# STM32_ESP.net
KiCad netlist of a schematic drawn in Altium Designer
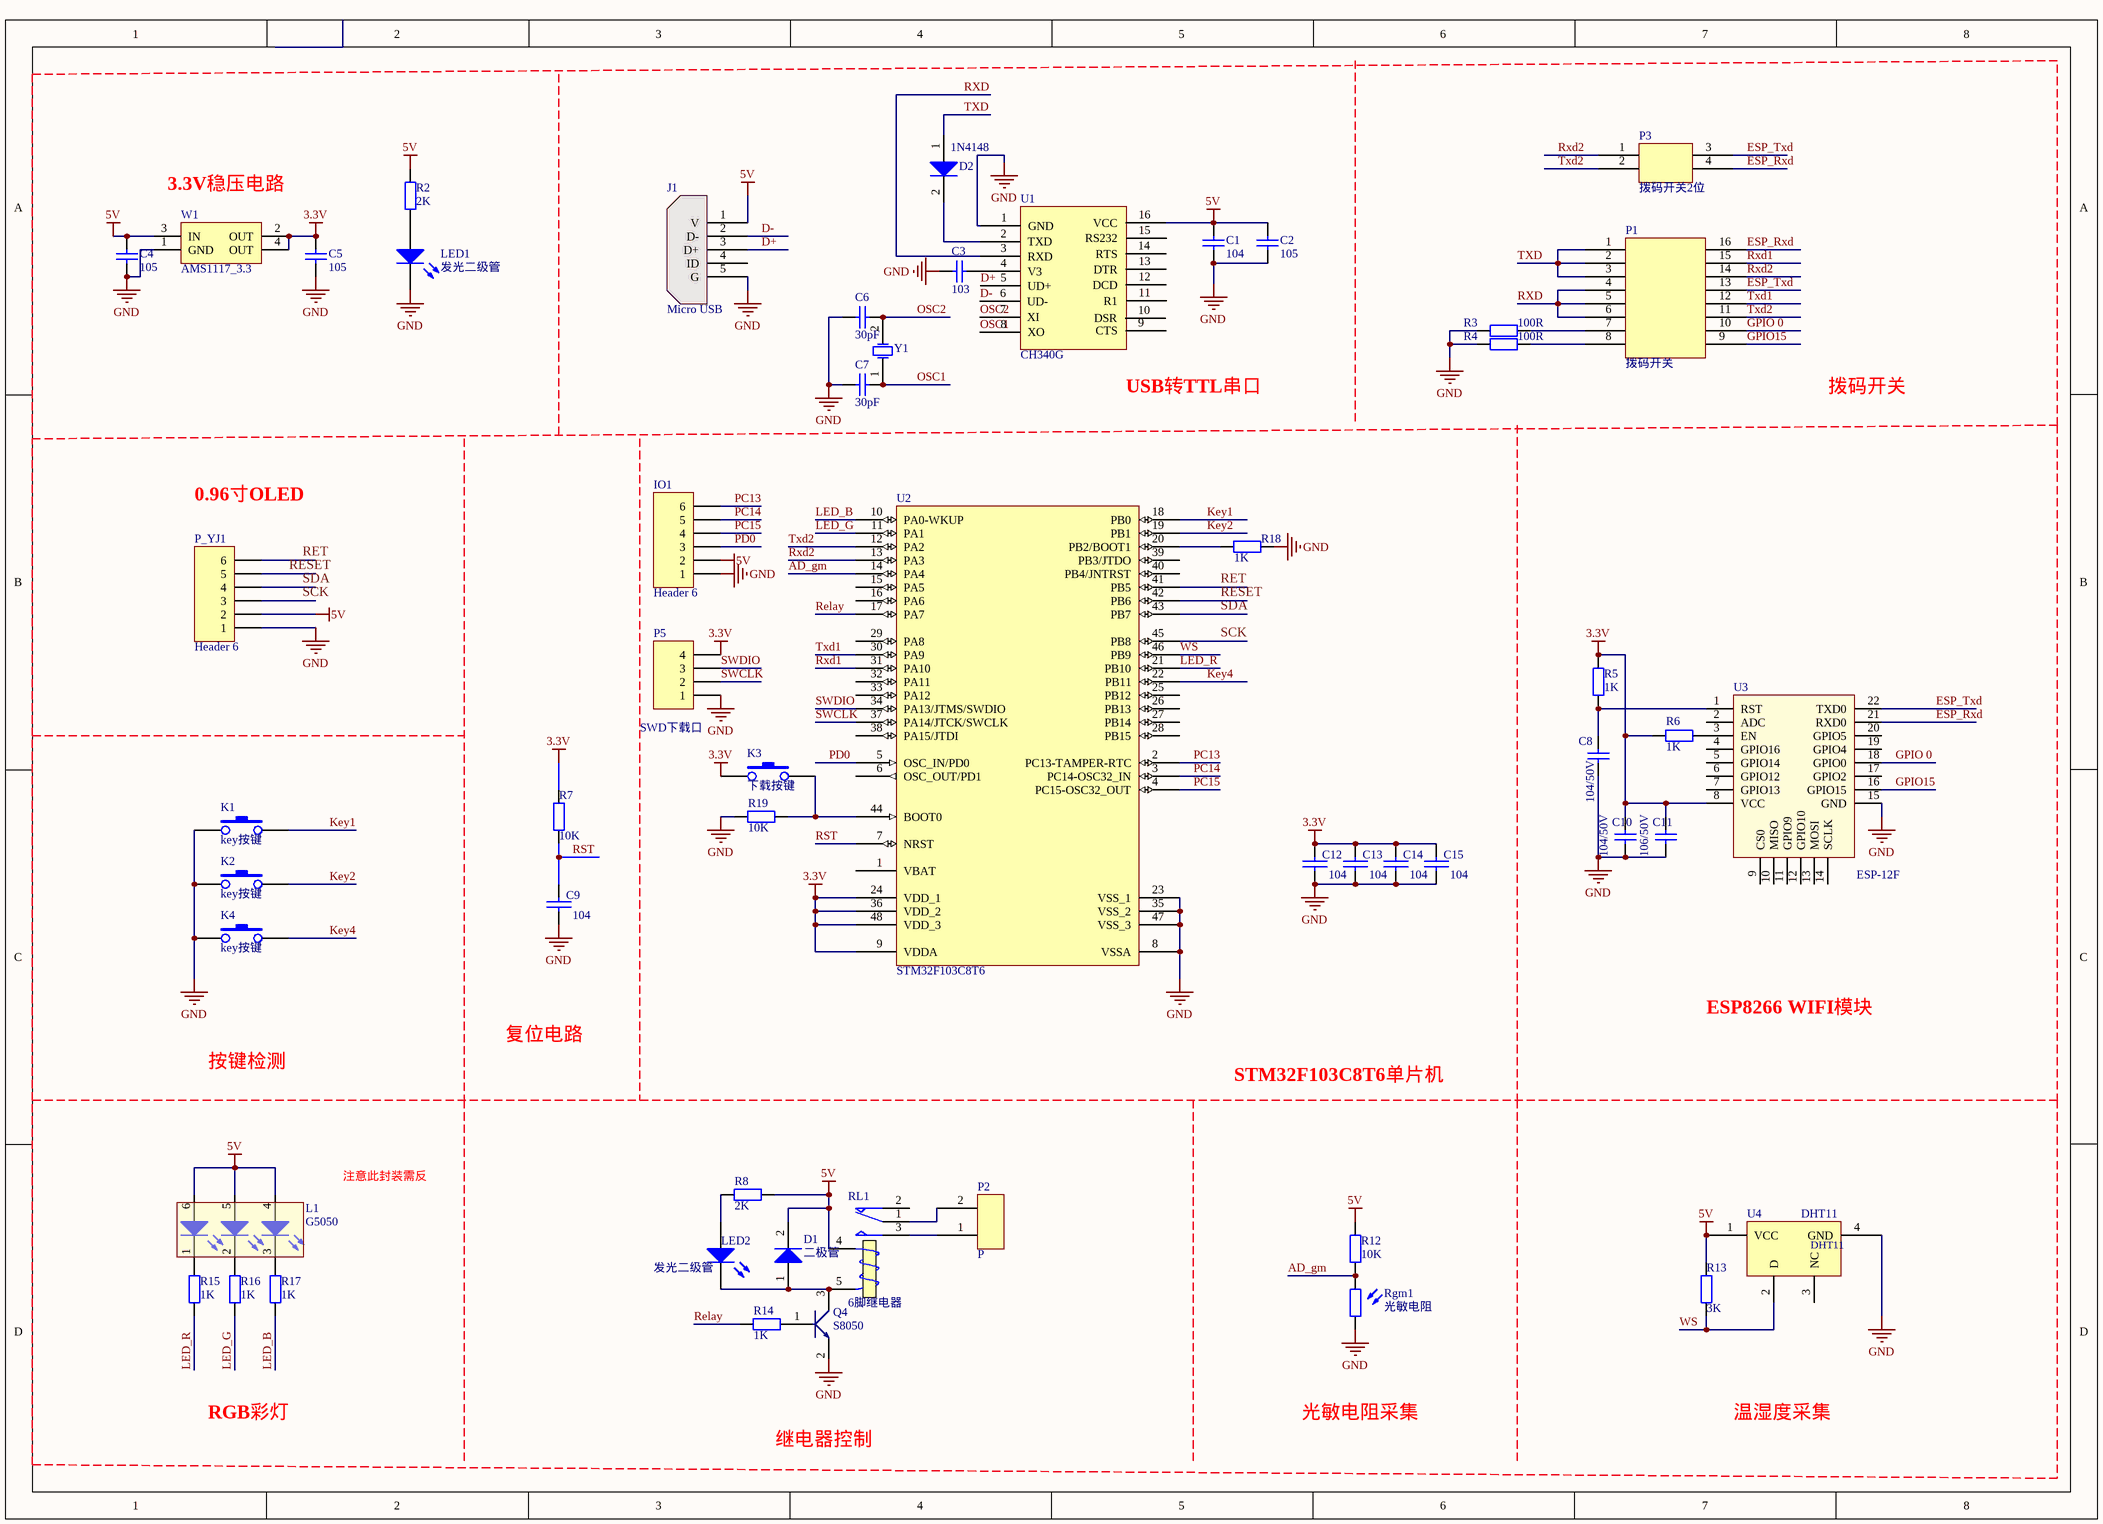
[diagram p0: STM32&ESP.SchDoc]

(export (version "E")
  (design (tool "Eeschema 10.0.6"))
  (components
    (comp (ref "C1")
      (value "104")
      (footprint "SC0603")
      (description "Capacitor")
      (fields (field (name "Comment") "Cap") (field (name "PUBLISHER") "Altium Limited"))
      (libsource (lib "myintlib") (part "Cap"))
    )
    (comp (ref "C2")
      (value "105")
      (footprint "SC0603")
      (description "Capacitor")
      (fields (field (name "Comment") "Cap") (field (name "PUBLISHER") "Altium Limited"))
      (libsource (lib "myintlib") (part "Cap"))
    )
    (comp (ref "C3")
      (value "103")
      (footprint "SC0603")
      (description "Capacitor")
      (fields (field (name "Comment") "Cap") (field (name "PUBLISHER") "Altium Limited"))
      (libsource (lib "myintlib") (part "Cap"))
    )
    (comp (ref "C4")
      (value "105")
      (footprint "SC0603")
      (description "Capacitor")
      (fields (field (name "Comment") "Cap") (field (name "PUBLISHER") "Altium Limited"))
      (libsource (lib "myintlib") (part "Cap"))
    )
    (comp (ref "C5")
      (value "105")
      (footprint "SC0603")
      (description "Capacitor")
      (fields (field (name "Comment") "Cap") (field (name "PUBLISHER") "Altium Limited"))
      (libsource (lib "myintlib") (part "Cap"))
    )
    (comp (ref "C6")
      (value "30pF")
      (footprint "SC0603")
      (description "Capacitor")
      (fields (field (name "Comment") "Cap") (field (name "PUBLISHER") "Altium Limited"))
      (libsource (lib "Miscellaneous Devices") (part "Cap"))
    )
    (comp (ref "C7")
      (value "30pF")
      (footprint "SC0603")
      (description "Capacitor")
      (fields (field (name "Comment") "Cap") (field (name "PUBLISHER") "Altium Limited"))
      (libsource (lib "Miscellaneous Devices") (part "Cap"))
    )
    (comp (ref "C8")
      (value "104/50V")
      (footprint "SC0603")
      (description "Capacitor (Semiconductor SIM Model)")
      (fields (field (name "MANUFACTURER") "风华高科"))
      (libsource (lib "Miscellaneous Devices") (part "Cap Semi"))
    )
    (comp (ref "C9")
      (value "104")
      (footprint "SC0603")
      (description "Capacitor")
      (libsource (lib "*") (part "CAP"))
    )
    (comp (ref "C10")
      (value "104/50V")
      (footprint "SC0603")
      (description "Capacitor (Semiconductor SIM Model)")
      (fields (field (name "MANUFACTURER") "风华高科"))
      (libsource (lib "Miscellaneous Devices") (part "Cap Semi"))
    )
    (comp (ref "C11")
      (value "106/50V")
      (footprint "SC0603")
      (description "Capacitor (Semiconductor SIM Model)")
      (fields (field (name "MANUFACTURER") "风华高科"))
      (libsource (lib "Miscellaneous Devices") (part "Cap Semi"))
    )
    (comp (ref "C12")
      (value "104")
      (footprint "SC0603")
      (description "Capacitor")
      (libsource (lib "*") (part "CAP"))
    )
    (comp (ref "C13")
      (value "104")
      (footprint "SC0603")
      (description "Capacitor")
      (libsource (lib "*") (part "CAP"))
    )
    (comp (ref "C14")
      (value "104")
      (footprint "SC0603")
      (description "Capacitor")
      (libsource (lib "*") (part "CAP"))
    )
    (comp (ref "C15")
      (value "104")
      (footprint "SC0603")
      (description "Capacitor")
      (libsource (lib "*") (part "CAP"))
    )
    (comp (ref "D1") (value "二极管") (footprint "SS12") (libsource (lib "单片机1") (part "二极管")))
    (comp (ref "D2") (value "1N4148") (footprint "SS12") (libsource (lib "单片机1") (part "二极管")))
    (comp (ref "IO1")
      (value "Header 6")
      (footprint "HDR1X6")
      (description "Header, 6-Pin")
      (fields (field (name "PUBLISHER") "Altium Limited"))
      (libsource (lib "Miscellaneous Connectors") (part "Header 6"))
    )
    (comp (ref "J1") (value "Micro USB") (footprint "micro usb") (libsource (lib "各种接插件") (part "Micro USB")))
    (comp (ref "K1") (value "key按键") (footprint "SW-T") (libsource (lib "单片机1") (part "key按键")))
    (comp (ref "K2") (value "key按键") (footprint "SW-T") (libsource (lib "单片机1") (part "key按键")))
    (comp (ref "K3") (value "下载按键") (footprint "轻触开关 3*6*2.5mm") (libsource (lib "单片机1") (part "key按键")))
    (comp (ref "K4") (value "key按键") (footprint "SW-T") (libsource (lib "单片机1") (part "key按键")))
    (comp (ref "L1") (value "G5050") (footprint "G5050") (libsource (lib "各种显示器件") (part "G5050")))
    (comp (ref "LED1") (value "发光二级管") (footprint "G0603") (libsource (lib "单片机1") (part "发光二级管")))
    (comp (ref "LED2") (value "发光二级管") (footprint "G0603") (libsource (lib "单片机1") (part "发光二级管")))
    (comp (ref "P1") (value "拨码开关") (footprint "拨码开关") (libsource (lib "单片机1") (part "拨码开关")))
    (comp (ref "P2") (value "P") (footprint "KF301-2P") (libsource (lib "各种接插件") (part "2P")))
    (comp (ref "P3") (value "拨码开关2位") (footprint "拨码开关2位") (libsource (lib "单片机1") (part "拨码开关2位")))
    (comp (ref "P5") (value "SWD下载口") (footprint "4P") (libsource (lib "单片机1") (part "4P")))
    (comp (ref "P_YJ1")
      (value "Header 6")
      (footprint "HDR1X6")
      (description "Header, 6-Pin")
      (fields (field (name "PUBLISHER") "Altium Limited"))
      (libsource (lib "Miscellaneous Connectors") (part "Header 6"))
    )
    (comp (ref "Q4") (value "S8050") (footprint "SOT-23") (libsource (lib "单片机1") (part "三极管3")))
    (comp (ref "R2") (value "2K") (footprint "0603R") (libsource (lib "单片机1") (part "电阻R")))
    (comp (ref "R3")
      (value "100R")
      (footprint "0603R")
      (fields (field (name "MANUFACTURER") "厚生"))
      (libsource (lib "YANG") (part "RES0.2"))
    )
    (comp (ref "R4")
      (value "100R")
      (footprint "0603R")
      (fields (field (name "MANUFACTURER") "厚生"))
      (libsource (lib "YANG") (part "RES0.2"))
    )
    (comp (ref "R5")
      (value "1K")
      (footprint "0603R")
      (fields (field (name "MANUFACTURER") "厚生"))
      (libsource (lib "") (part "RES0.2_1"))
    )
    (comp (ref "R6")
      (value "1K")
      (footprint "0603R")
      (fields (field (name "MANUFACTURER") "厚生"))
      (libsource (lib "YANG") (part "RES0.2"))
    )
    (comp (ref "R7")
      (value "1K")
      (footprint "0603R")
      (fields (field (name "ALTIUM_UNNAMED_1") "10K"))
      (libsource (lib "") (part "RES0.4_1"))
    )
    (comp (ref "R8") (value "2K") (footprint "0603R") (libsource (lib "") (part "电阻R_1")))
    (comp (ref "R12")
      (value "10K")
      (footprint "0603R")
      (fields (field (name "MANUFACTURER") "厚生"))
      (libsource (lib "") (part "RES0.2_1"))
    )
    (comp (ref "R13")
      (value "1K")
      (footprint "0603R")
      (fields (field (name "ALTIUM_UNNAMED_1") "3K"))
      (libsource (lib "YANG") (part "RES0.4"))
    )
    (comp (ref "R14")
      (value "1K")
      (footprint "0603R")
      (fields (field (name "MANUFACTURER") "厚生"))
      (libsource (lib "YANG") (part "RES0.2"))
    )
    (comp (ref "R15")
      (value "1K")
      (footprint "0603R")
      (fields (field (name "MANUFACTURER") "厚生"))
      (libsource (lib "") (part "RES0.2_1"))
    )
    (comp (ref "R16")
      (value "1K")
      (footprint "0603R")
      (fields (field (name "MANUFACTURER") "厚生"))
      (libsource (lib "") (part "RES0.2_1"))
    )
    (comp (ref "R17")
      (value "1K")
      (footprint "0603R")
      (fields (field (name "MANUFACTURER") "厚生"))
      (libsource (lib "") (part "RES0.2_1"))
    )
    (comp (ref "R18")
      (value "1K")
      (footprint "0603R")
      (fields (field (name "MANUFACTURER") "厚生"))
      (libsource (lib "") (part "RES0.2_2"))
    )
    (comp (ref "R19")
      (value "10K")
      (footprint "0603R")
      (fields (field (name "MANUFACTURER") "厚生"))
      (libsource (lib "YANG") (part "RES0.2"))
    )
    (comp (ref "Rgm1") (value "光敏电阻") (footprint "pr") (libsource (lib "电阻") (part "Res-Sen")))
    (comp (ref "RL1") (value "6脚继电器") (footprint "6脚继电器") (libsource (lib "单片机1") (part "6脚继电器")))
    (comp (ref "U1") (value "CH340G") (footprint "MAX3232") (libsource (lib "单片机1") (part "CH340G")))
    (comp (ref "U2")
      (value "STM32F103C8T6")
      (footprint "LQFP-48_M")
      (libsource (lib "单片机1") (part "STM32F103C8T6"))
    )
    (comp (ref "U3")
      (value "ESP-12F")
      (footprint "ESP12F")
      (fields (field (name "MANUFACTURER") "安信可"))
      (libsource (lib "其他") (part "ESP-12F"))
    )
    (comp (ref "U4") (value "DHT11") (footprint "DHT11") (libsource (lib "其他") (part "DHT11")))
    (comp (ref "W1")
      (value "AMS1117_3.3")
      (footprint "AMS1117_3.3")
      (libsource (lib "单片机1") (part "AMS1117_3.3"))
    )
    (comp (ref "Y1")
      (value "XTAL")
      (footprint "XTAX5")
      (description "Crystal Oscillator")
      (fields (field (name "PUBLISHER") "Altium Limited"))
      (libsource (lib "Miscellaneous Devices") (part "XTAL"))
    )
  )
  (nets
    (net (code "1") (name "/AD_gm") (class "Default")
      (node (ref "R12") (pin "1") (pinfunction "1_1") (pintype "passive"))
      (node (ref "Rgm1") (pin "1") (pinfunction "1_1") (pintype "passive"))
      (node (ref "U2") (pin "14") (pinfunction "PA4_14") (pintype "bidirectional"))
    )
    (net (code "2") (name "/D+") (class "Default")
      (node (ref "J1") (pin "3") (pinfunction "D+_3") (pintype "passive"))
      (node (ref "U1") (pin "5") (pinfunction "UD+_5") (pintype "passive"))
    )
    (net (code "3") (name "/D-") (class "Default")
      (node (ref "J1") (pin "2") (pinfunction "D-_2") (pintype "passive"))
      (node (ref "U1") (pin "6") (pinfunction "UD-_6") (pintype "passive"))
    )
    (net (code "4") (name "/ESP_Rxd") (class "Default")
      (node (ref "P1") (pin "16") (pinfunction "16_16") (pintype "passive"))
      (node (ref "P3") (pin "4") (pinfunction "4_4") (pintype "passive"))
      (node (ref "U3") (pin "21") (pinfunction "RXD0_21") (pintype "passive"))
    )
    (net (code "5") (name "/ESP_Txd") (class "Default")
      (node (ref "P1") (pin "13") (pinfunction "13_13") (pintype "passive"))
      (node (ref "P3") (pin "3") (pinfunction "3_3") (pintype "passive"))
      (node (ref "U3") (pin "22") (pinfunction "TXD0_22") (pintype "passive"))
    )
    (net (code "6") (name "/GPIO 0") (class "Default")
      (node (ref "P1") (pin "10") (pinfunction "10_10") (pintype "passive"))
      (node (ref "U3") (pin "18") (pinfunction "GPIO0_18") (pintype "passive"))
    )
    (net (code "7") (name "/GPIO15") (class "Default")
      (node (ref "P1") (pin "9") (pinfunction "9_9") (pintype "passive"))
      (node (ref "U3") (pin "16") (pinfunction "GPIO15_16") (pintype "passive"))
    )
    (net (code "8") (name "/Key1") (class "Default")
      (node (ref "K1") (pin "2") (pinfunction "2_2") (pintype "passive"))
      (node (ref "U2") (pin "18") (pinfunction "PB0_18") (pintype "bidirectional"))
    )
    (net (code "9") (name "/Key2") (class "Default")
      (node (ref "K2") (pin "2") (pinfunction "2_2") (pintype "passive"))
      (node (ref "U2") (pin "19") (pinfunction "PB1_19") (pintype "bidirectional"))
    )
    (net (code "10") (name "/Key4") (class "Default")
      (node (ref "K4") (pin "2") (pinfunction "2_2") (pintype "passive"))
      (node (ref "U2") (pin "22") (pinfunction "PB11_22") (pintype "bidirectional"))
    )
    (net (code "11") (name "/LED_B") (class "Default")
      (node (ref "R17") (pin "1") (pinfunction "1_1") (pintype "passive"))
      (node (ref "U2") (pin "10") (pinfunction "PA0-WKUP_10") (pintype "bidirectional"))
    )
    (net (code "12") (name "/LED_G") (class "Default")
      (node (ref "R16") (pin "1") (pinfunction "1_1") (pintype "passive"))
      (node (ref "U2") (pin "11") (pinfunction "PA1_11") (pintype "bidirectional"))
    )
    (net (code "13") (name "/LED_R") (class "Default")
      (node (ref "R15") (pin "1") (pinfunction "1_1") (pintype "passive"))
      (node (ref "U2") (pin "21") (pinfunction "PB10_21") (pintype "bidirectional"))
    )
    (net (code "14") (name "/OSC1") (class "Default")
      (node (ref "C7") (pin "1") (pinfunction "1_1") (pintype "passive"))
      (node (ref "U1") (pin "8") (pinfunction "XO_8") (pintype "passive"))
      (node (ref "Y1") (pin "1") (pinfunction "OSC1_1") (pintype "passive"))
    )
    (net (code "15") (name "/OSC2") (class "Default")
      (node (ref "C6") (pin "1") (pinfunction "1_1") (pintype "passive"))
      (node (ref "U1") (pin "7") (pinfunction "XI_7") (pintype "passive"))
      (node (ref "Y1") (pin "2") (pinfunction "OSC2_2") (pintype "passive"))
    )
    (net (code "16") (name "/PC13") (class "Default")
      (node (ref "IO1") (pin "6") (pinfunction "6_6") (pintype "passive"))
      (node (ref "U2") (pin "2") (pinfunction "PC13-TAMPER-RTC_2") (pintype "bidirectional"))
    )
    (net (code "17") (name "/PC14") (class "Default")
      (node (ref "IO1") (pin "5") (pinfunction "5_5") (pintype "passive"))
      (node (ref "U2") (pin "3") (pinfunction "PC14-OSC32_IN_3") (pintype "bidirectional"))
    )
    (net (code "18") (name "/PC15") (class "Default")
      (node (ref "IO1") (pin "4") (pinfunction "4_4") (pintype "passive"))
      (node (ref "U2") (pin "4") (pinfunction "PC15-OSC32_OUT_4") (pintype "bidirectional"))
    )
    (net (code "19") (name "/PD0") (class "Default")
      (node (ref "IO1") (pin "3") (pinfunction "3_3") (pintype "passive"))
      (node (ref "U2") (pin "5") (pinfunction "OSC_IN/PD0_5") (pintype "input"))
    )
    (net (code "20") (name "/RESET") (class "Default")
      (node (ref "P_YJ1") (pin "5") (pinfunction "5_5") (pintype "passive"))
      (node (ref "U2") (pin "42") (pinfunction "PB6_42") (pintype "bidirectional"))
    )
    (net (code "21") (name "/RET") (class "Default")
      (node (ref "P_YJ1") (pin "6") (pinfunction "6_6") (pintype "passive"))
      (node (ref "U2") (pin "41") (pinfunction "PB5_41") (pintype "bidirectional"))
    )
    (net (code "22") (name "/RST") (class "Default")
      (node (ref "C9") (pin "1") (pinfunction "1_1") (pintype "passive"))
      (node (ref "R7") (pin "1") (pinfunction "1_1") (pintype "passive"))
      (node (ref "U2") (pin "7") (pinfunction "NRST_7") (pintype "bidirectional"))
    )
    (net (code "23") (name "/RXD") (class "Default")
      (node (ref "P1") (pin "4") (pinfunction "4_4") (pintype "passive"))
      (node (ref "P1") (pin "5") (pinfunction "5_5") (pintype "passive"))
      (node (ref "P1") (pin "6") (pinfunction "6_6") (pintype "passive"))
      (node (ref "U1") (pin "3") (pinfunction "RXD_3") (pintype "passive"))
    )
    (net (code "24") (name "/Relay") (class "Default")
      (node (ref "R14") (pin "1") (pinfunction "1_1") (pintype "passive"))
      (node (ref "U2") (pin "17") (pinfunction "PA7_17") (pintype "bidirectional"))
    )
    (net (code "25") (name "/Rxd1") (class "Default")
      (node (ref "P1") (pin "15") (pinfunction "15_15") (pintype "passive"))
      (node (ref "U2") (pin "31") (pinfunction "PA10_31") (pintype "bidirectional"))
    )
    (net (code "26") (name "/Rxd2") (class "Default")
      (node (ref "P1") (pin "14") (pinfunction "14_14") (pintype "passive"))
      (node (ref "P3") (pin "1") (pinfunction "1_1") (pintype "passive"))
      (node (ref "U2") (pin "13") (pinfunction "PA3_13") (pintype "bidirectional"))
    )
    (net (code "27") (name "/SCK") (class "Default")
      (node (ref "P_YJ1") (pin "3") (pinfunction "3_3") (pintype "passive"))
      (node (ref "U2") (pin "45") (pinfunction "PB8_45") (pintype "bidirectional"))
    )
    (net (code "28") (name "/SDA") (class "Default")
      (node (ref "P_YJ1") (pin "4") (pinfunction "4_4") (pintype "passive"))
      (node (ref "U2") (pin "43") (pinfunction "PB7_43") (pintype "bidirectional"))
    )
    (net (code "29") (name "/SWCLK") (class "Default")
      (node (ref "P5") (pin "2") (pinfunction "2_2") (pintype "passive"))
      (node (ref "U2") (pin "37") (pinfunction "PA14/JTCK/SWCLK_37") (pintype "bidirectional"))
    )
    (net (code "30") (name "/SWDIO") (class "Default")
      (node (ref "P5") (pin "3") (pinfunction "3_3") (pintype "passive"))
      (node (ref "U2") (pin "34") (pinfunction "PA13/JTMS/SWDIO_34") (pintype "bidirectional"))
    )
    (net (code "31") (name "/TXD") (class "Default")
      (node (ref "D2") (pin "1") (pinfunction "A_1") (pintype "passive"))
      (node (ref "P1") (pin "1") (pinfunction "1_1") (pintype "passive"))
      (node (ref "P1") (pin "2") (pinfunction "2_2") (pintype "passive"))
      (node (ref "P1") (pin "3") (pinfunction "3_3") (pintype "passive"))
    )
    (net (code "32") (name "/Txd1") (class "Default")
      (node (ref "P1") (pin "12") (pinfunction "12_12") (pintype "passive"))
      (node (ref "U2") (pin "30") (pinfunction "PA9_30") (pintype "bidirectional"))
    )
    (net (code "33") (name "/Txd2") (class "Default")
      (node (ref "P1") (pin "11") (pinfunction "11_11") (pintype "passive"))
      (node (ref "P3") (pin "2") (pinfunction "2_2") (pintype "passive"))
      (node (ref "U2") (pin "12") (pinfunction "PA2_12") (pintype "bidirectional"))
    )
    (net (code "34") (name "/WS") (class "Default")
      (node (ref "R13") (pin "2") (pinfunction "2_2") (pintype "passive"))
      (node (ref "U2") (pin "46") (pinfunction "PB9_46") (pintype "bidirectional"))
      (node (ref "U4") (pin "2") (pinfunction "D_2") (pintype "passive"))
    )
    (net (code "35") (name "3.3V") (class "Default")
      (node (ref "C10") (pin "1") (pinfunction "1_1") (pintype "passive"))
      (node (ref "C11") (pin "1") (pinfunction "1_1") (pintype "passive"))
      (node (ref "C12") (pin "1") (pinfunction "1_1") (pintype "passive"))
      (node (ref "C13") (pin "1") (pinfunction "1_1") (pintype "passive"))
      (node (ref "C14") (pin "1") (pinfunction "1_1") (pintype "passive"))
      (node (ref "C15") (pin "1") (pinfunction "1_1") (pintype "passive"))
      (node (ref "C5") (pin "2") (pinfunction "2_2") (pintype "passive"))
      (node (ref "K3") (pin "1") (pinfunction "1_1") (pintype "passive"))
      (node (ref "P5") (pin "4") (pinfunction "4_4") (pintype "passive"))
      (node (ref "R5") (pin "2") (pinfunction "2_2") (pintype "passive"))
      (node (ref "R6") (pin "1") (pinfunction "1_1") (pintype "passive"))
      (node (ref "R7") (pin "2") (pinfunction "2_2") (pintype "passive"))
      (node (ref "U2") (pin "24") (pinfunction "VDD_1_24") (pintype "power_in"))
      (node (ref "U2") (pin "36") (pinfunction "VDD_2_36") (pintype "power_in"))
      (node (ref "U2") (pin "48") (pinfunction "VDD_3_48") (pintype "power_in"))
      (node (ref "U2") (pin "9") (pinfunction "VDDA_9") (pintype "power_in"))
      (node (ref "U3") (pin "8") (pinfunction "VCC_8") (pintype "passive"))
      (node (ref "W1") (pin "2") (pinfunction "OUT_2") (pintype "power_in"))
      (node (ref "W1") (pin "4") (pinfunction "OUT_4") (pintype "power_in"))
    )
    (net (code "36") (name "5V") (class "Default")
      (node (ref "C1") (pin "2") (pinfunction "2_2") (pintype "passive"))
      (node (ref "C2") (pin "2") (pinfunction "2_2") (pintype "passive"))
      (node (ref "C4") (pin "2") (pinfunction "2_2") (pintype "passive"))
      (node (ref "D1") (pin "2") (pinfunction "K_2") (pintype "passive"))
      (node (ref "IO1") (pin "2") (pinfunction "2_2") (pintype "passive"))
      (node (ref "J1") (pin "1") (pinfunction "V_1") (pintype "passive"))
      (node (ref "L1") (pin "4") (pinfunction "A_4") (pintype "passive"))
      (node (ref "L1") (pin "5") (pinfunction "A_5") (pintype "passive"))
      (node (ref "L1") (pin "6") (pinfunction "A_6") (pintype "passive"))
      (node (ref "P_YJ1") (pin "2") (pinfunction "2_2") (pintype "passive"))
      (node (ref "R12") (pin "2") (pinfunction "2_2") (pintype "passive"))
      (node (ref "R13") (pin "1") (pinfunction "1_1") (pintype "passive"))
      (node (ref "R2") (pin "2") (pinfunction "2_2") (pintype "passive"))
      (node (ref "R8") (pin "1") (pinfunction "1_1") (pintype "passive"))
      (node (ref "RL1") (pin "4") (pinfunction "T1_4") (pintype "passive"))
      (node (ref "U1") (pin "16") (pinfunction "VCC_16") (pintype "passive"))
      (node (ref "U4") (pin "1") (pinfunction "VCC_1") (pintype "passive"))
      (node (ref "W1") (pin "3") (pinfunction "IN_3") (pintype "power_in"))
    )
    (net (code "37") (name "GND") (class "Default")
      (node (ref "C1") (pin "1") (pinfunction "1_1") (pintype "passive"))
      (node (ref "C10") (pin "2") (pinfunction "2_2") (pintype "passive"))
      (node (ref "C11") (pin "2") (pinfunction "2_2") (pintype "passive"))
      (node (ref "C12") (pin "2") (pinfunction "2_2") (pintype "passive"))
      (node (ref "C13") (pin "2") (pinfunction "2_2") (pintype "passive"))
      (node (ref "C14") (pin "2") (pinfunction "2_2") (pintype "passive"))
      (node (ref "C15") (pin "2") (pinfunction "2_2") (pintype "passive"))
      (node (ref "C2") (pin "1") (pinfunction "1_1") (pintype "passive"))
      (node (ref "C3") (pin "2") (pinfunction "2_2") (pintype "passive"))
      (node (ref "C4") (pin "1") (pinfunction "1_1") (pintype "passive"))
      (node (ref "C5") (pin "1") (pinfunction "1_1") (pintype "passive"))
      (node (ref "C6") (pin "2") (pinfunction "2_2") (pintype "passive"))
      (node (ref "C7") (pin "2") (pinfunction "2_2") (pintype "passive"))
      (node (ref "C8") (pin "2") (pinfunction "2_2") (pintype "passive"))
      (node (ref "C9") (pin "2") (pinfunction "2_2") (pintype "passive"))
      (node (ref "IO1") (pin "1") (pinfunction "1_1") (pintype "passive"))
      (node (ref "J1") (pin "5") (pinfunction "G_5") (pintype "passive"))
      (node (ref "K1") (pin "1") (pinfunction "1_1") (pintype "passive"))
      (node (ref "K2") (pin "1") (pinfunction "1_1") (pintype "passive"))
      (node (ref "K4") (pin "1") (pinfunction "1_1") (pintype "passive"))
      (node (ref "LED1") (pin "2") (pinfunction "K_2") (pintype "passive"))
      (node (ref "P5") (pin "1") (pinfunction "1_1") (pintype "passive"))
      (node (ref "P_YJ1") (pin "1") (pinfunction "1_1") (pintype "passive"))
      (node (ref "Q4") (pin "2") (pinfunction "2_2") (pintype "passive"))
      (node (ref "R18") (pin "1") (pinfunction "1_1") (pintype "passive"))
      (node (ref "R19") (pin "1") (pinfunction "1_1") (pintype "passive"))
      (node (ref "R3") (pin "1") (pinfunction "1_1") (pintype "passive"))
      (node (ref "R4") (pin "1") (pinfunction "1_1") (pintype "passive"))
      (node (ref "Rgm1") (pin "2") (pinfunction "2_2") (pintype "passive"))
      (node (ref "U1") (pin "1") (pinfunction "GND_1") (pintype "passive"))
      (node (ref "U2") (pin "23") (pinfunction "VSS_1_23") (pintype "power_in"))
      (node (ref "U2") (pin "35") (pinfunction "VSS_2_35") (pintype "power_in"))
      (node (ref "U2") (pin "47") (pinfunction "VSS_3_47") (pintype "power_in"))
      (node (ref "U2") (pin "8") (pinfunction "VSSA_8") (pintype "power_in"))
      (node (ref "U3") (pin "15") (pinfunction "GND_15") (pintype "passive"))
      (node (ref "U4") (pin "4") (pinfunction "GND_4") (pintype "passive"))
      (node (ref "W1") (pin "1") (pinfunction "GND_1") (pintype "power_in"))
    )
    (net (code "38") (name "Net-(D1-A)") (class "Default")
      (node (ref "D1") (pin "1") (pinfunction "A_1") (pintype "passive"))
      (node (ref "LED2") (pin "2") (pinfunction "K_2") (pintype "passive"))
      (node (ref "Q4") (pin "3") (pinfunction "3_3") (pintype "passive"))
      (node (ref "RL1") (pin "5") (pinfunction "T2_5") (pintype "passive"))
    )
    (net (code "39") (name "Net-(D2-K)") (class "Default")
      (node (ref "D2") (pin "2") (pinfunction "K_2") (pintype "passive"))
      (node (ref "U1") (pin "2") (pinfunction "TXD_2") (pintype "passive"))
    )
    (net (code "40") (name "Net-(L1-K-Pad1)") (class "Default")
      (node (ref "L1") (pin "1") (pinfunction "K_1") (pintype "passive"))
      (node (ref "R15") (pin "2") (pinfunction "2_2") (pintype "passive"))
    )
    (net (code "41") (name "Net-(L1-K-Pad2)") (class "Default")
      (node (ref "L1") (pin "2") (pinfunction "K_2") (pintype "passive"))
      (node (ref "R16") (pin "2") (pinfunction "2_2") (pintype "passive"))
    )
    (net (code "42") (name "Net-(L1-K-Pad3)") (class "Default")
      (node (ref "L1") (pin "3") (pinfunction "K_3") (pintype "passive"))
      (node (ref "R17") (pin "2") (pinfunction "2_2") (pintype "passive"))
    )
    (net (code "43") (name "Net-(LED1-A)") (class "Default")
      (node (ref "LED1") (pin "1") (pinfunction "A_1") (pintype "passive"))
      (node (ref "R2") (pin "1") (pinfunction "1_1") (pintype "passive"))
    )
    (net (code "44") (name "Net-(LED2-A)") (class "Default")
      (node (ref "LED2") (pin "1") (pinfunction "A_1") (pintype "passive"))
      (node (ref "R8") (pin "2") (pinfunction "2_2") (pintype "passive"))
    )
    (net (code "45") (name "Net-(P1-Pad7)") (class "Default")
      (node (ref "P1") (pin "7") (pinfunction "7_7") (pintype "passive"))
      (node (ref "R3") (pin "2") (pinfunction "2_2") (pintype "passive"))
    )
    (net (code "46") (name "Net-(P1-Pad8)") (class "Default")
      (node (ref "P1") (pin "8") (pinfunction "8_8") (pintype "passive"))
      (node (ref "R4") (pin "2") (pinfunction "2_2") (pintype "passive"))
    )
    (net (code "47") (name "Net-(Q4-Pad1)") (class "Default")
      (node (ref "Q4") (pin "1") (pinfunction "1_1") (pintype "passive"))
      (node (ref "R14") (pin "2") (pinfunction "2_2") (pintype "passive"))
    )
    (net (code "48") (name "Net-(RL1-COM)") (class "Default")
      (node (ref "P2") (pin "2") (pinfunction "2_2") (pintype "passive"))
      (node (ref "RL1") (pin "1") (pinfunction "COM_1") (pintype "passive"))
    )
    (net (code "49") (name "Net-(RL1-NO)") (class "Default")
      (node (ref "P2") (pin "1") (pinfunction "1_1") (pintype "passive"))
      (node (ref "RL1") (pin "3") (pinfunction "NO_3") (pintype "passive"))
    )
    (net (code "50") (name "Net-(U1-V3)") (class "Default")
      (node (ref "C3") (pin "1") (pinfunction "1_1") (pintype "passive"))
      (node (ref "U1") (pin "4") (pinfunction "V3_4") (pintype "passive"))
    )
    (net (code "51") (name "Net-(U2-BOOT0)") (class "Default")
      (node (ref "K3") (pin "2") (pinfunction "2_2") (pintype "passive"))
      (node (ref "R19") (pin "2") (pinfunction "2_2") (pintype "passive"))
      (node (ref "U2") (pin "44") (pinfunction "BOOT0_44") (pintype "input"))
    )
    (net (code "52") (name "Net-(U2-PB2{slash}BOOT1)") (class "Default")
      (node (ref "R18") (pin "2") (pinfunction "2_2") (pintype "passive"))
      (node (ref "U2") (pin "20") (pinfunction "PB2/BOOT1_20") (pintype "bidirectional"))
    )
    (net (code "53") (name "Net-(U3-EN)") (class "Default")
      (node (ref "R6") (pin "2") (pinfunction "2_2") (pintype "passive"))
      (node (ref "U3") (pin "3") (pinfunction "EN_3") (pintype "passive"))
    )
    (net (code "54") (name "Net-(U3-RST)") (class "Default")
      (node (ref "C8") (pin "1") (pinfunction "1_1") (pintype "passive"))
      (node (ref "R5") (pin "1") (pinfunction "1_1") (pintype "passive"))
      (node (ref "U3") (pin "1") (pinfunction "RST_1") (pintype "passive"))
    )
    (net (code "55") (name "unconnected-(J1-ID-Pad4)") (class "Default")
      (node (ref "J1") (pin "4") (pinfunction "ID_4") (pintype "passive"))
    )
    (net (code "56") (name "unconnected-(RL1-NC-Pad2)") (class "Default")
      (node (ref "RL1") (pin "2") (pinfunction "NC_2") (pintype "passive"))
    )
    (net (code "57") (name "unconnected-(U1-CTS-Pad9)") (class "Default")
      (node (ref "U1") (pin "9") (pinfunction "CTS_9") (pintype "passive"))
    )
    (net (code "58") (name "unconnected-(U1-DCD-Pad12)") (class "Default")
      (node (ref "U1") (pin "12") (pinfunction "DCD_12") (pintype "passive"))
    )
    (net (code "59") (name "unconnected-(U1-DSR-Pad10)") (class "Default")
      (node (ref "U1") (pin "10") (pinfunction "DSR_10") (pintype "passive"))
    )
    (net (code "60") (name "unconnected-(U1-DTR-Pad13)") (class "Default")
      (node (ref "U1") (pin "13") (pinfunction "DTR_13") (pintype "passive"))
    )
    (net (code "61") (name "unconnected-(U1-R1-Pad11)") (class "Default")
      (node (ref "U1") (pin "11") (pinfunction "R1_11") (pintype "passive"))
    )
    (net (code "62") (name "unconnected-(U1-RS232-Pad15)") (class "Default")
      (node (ref "U1") (pin "15") (pinfunction "RS232_15") (pintype "passive"))
    )
    (net (code "63") (name "unconnected-(U1-RTS-Pad14)") (class "Default")
      (node (ref "U1") (pin "14") (pinfunction "RTS_14") (pintype "passive"))
    )
    (net (code "64") (name "unconnected-(U2-OSC_OUT{slash}PD1-Pad6)") (class "Default")
      (node (ref "U2") (pin "6") (pinfunction "OSC_OUT/PD1_6") (pintype "output"))
    )
    (net (code "65") (name "unconnected-(U2-PA5-Pad15)") (class "Default")
      (node (ref "U2") (pin "15") (pinfunction "PA5_15") (pintype "bidirectional"))
    )
    (net (code "66") (name "unconnected-(U2-PA6-Pad16)") (class "Default")
      (node (ref "U2") (pin "16") (pinfunction "PA6_16") (pintype "bidirectional"))
    )
    (net (code "67") (name "unconnected-(U2-PA8-Pad29)") (class "Default")
      (node (ref "U2") (pin "29") (pinfunction "PA8_29") (pintype "bidirectional"))
    )
    (net (code "68") (name "unconnected-(U2-PA11-Pad32)") (class "Default")
      (node (ref "U2") (pin "32") (pinfunction "PA11_32") (pintype "bidirectional"))
    )
    (net (code "69") (name "unconnected-(U2-PA12-Pad33)") (class "Default")
      (node (ref "U2") (pin "33") (pinfunction "PA12_33") (pintype "bidirectional"))
    )
    (net (code "70") (name "unconnected-(U2-PA15{slash}JTDI-Pad38)") (class "Default")
      (node (ref "U2") (pin "38") (pinfunction "PA15/JTDI_38") (pintype "bidirectional"))
    )
    (net (code "71") (name "unconnected-(U2-PB3{slash}JTDO-Pad39)") (class "Default")
      (node (ref "U2") (pin "39") (pinfunction "PB3/JTDO_39") (pintype "bidirectional"))
    )
    (net (code "72") (name "unconnected-(U2-PB4{slash}JNTRST-Pad40)") (class "Default")
      (node (ref "U2") (pin "40") (pinfunction "PB4/JNTRST_40") (pintype "bidirectional"))
    )
    (net (code "73") (name "unconnected-(U2-PB12-Pad25)") (class "Default")
      (node (ref "U2") (pin "25") (pinfunction "PB12_25") (pintype "bidirectional"))
    )
    (net (code "74") (name "unconnected-(U2-PB13-Pad26)") (class "Default")
      (node (ref "U2") (pin "26") (pinfunction "PB13_26") (pintype "bidirectional"))
    )
    (net (code "75") (name "unconnected-(U2-PB14-Pad27)") (class "Default")
      (node (ref "U2") (pin "27") (pinfunction "PB14_27") (pintype "bidirectional"))
    )
    (net (code "76") (name "unconnected-(U2-PB15-Pad28)") (class "Default")
      (node (ref "U2") (pin "28") (pinfunction "PB15_28") (pintype "bidirectional"))
    )
    (net (code "77") (name "unconnected-(U2-VBAT-Pad1)") (class "Default")
      (node (ref "U2") (pin "1") (pinfunction "VBAT_1") (pintype "power_in"))
    )
    (net (code "78") (name "unconnected-(U3-ADC-Pad2)") (class "Default")
      (node (ref "U3") (pin "2") (pinfunction "ADC_2") (pintype "passive"))
    )
    (net (code "79") (name "unconnected-(U3-CS0-Pad9)") (class "Default")
      (node (ref "U3") (pin "9") (pinfunction "CS0_9") (pintype "passive"))
    )
    (net (code "80") (name "unconnected-(U3-GPIO2-Pad17)") (class "Default")
      (node (ref "U3") (pin "17") (pinfunction "GPIO2_17") (pintype "passive"))
    )
    (net (code "81") (name "unconnected-(U3-GPIO4-Pad19)") (class "Default")
      (node (ref "U3") (pin "19") (pinfunction "GPIO4_19") (pintype "passive"))
    )
    (net (code "82") (name "unconnected-(U3-GPIO5-Pad20)") (class "Default")
      (node (ref "U3") (pin "20") (pinfunction "GPIO5_20") (pintype "passive"))
    )
    (net (code "83") (name "unconnected-(U3-GPIO9-Pad11)") (class "Default")
      (node (ref "U3") (pin "11") (pinfunction "GPIO9_11") (pintype "passive"))
    )
    (net (code "84") (name "unconnected-(U3-GPIO10-Pad12)") (class "Default")
      (node (ref "U3") (pin "12") (pinfunction "GPIO10_12") (pintype "passive"))
    )
    (net (code "85") (name "unconnected-(U3-GPIO12-Pad6)") (class "Default")
      (node (ref "U3") (pin "6") (pinfunction "GPIO12_6") (pintype "passive"))
    )
    (net (code "86") (name "unconnected-(U3-GPIO13-Pad7)") (class "Default")
      (node (ref "U3") (pin "7") (pinfunction "GPIO13_7") (pintype "passive"))
    )
    (net (code "87") (name "unconnected-(U3-GPIO14-Pad5)") (class "Default")
      (node (ref "U3") (pin "5") (pinfunction "GPIO14_5") (pintype "passive"))
    )
    (net (code "88") (name "unconnected-(U3-GPIO16-Pad4)") (class "Default")
      (node (ref "U3") (pin "4") (pinfunction "GPIO16_4") (pintype "passive"))
    )
    (net (code "89") (name "unconnected-(U3-MISO-Pad10)") (class "Default")
      (node (ref "U3") (pin "10") (pinfunction "MISO_10") (pintype "passive"))
    )
    (net (code "90") (name "unconnected-(U3-MOSI-Pad13)") (class "Default")
      (node (ref "U3") (pin "13") (pinfunction "MOSI_13") (pintype "passive"))
    )
    (net (code "91") (name "unconnected-(U3-SCLK-Pad14)") (class "Default")
      (node (ref "U3") (pin "14") (pinfunction "SCLK_14") (pintype "passive"))
    )
    (net (code "92") (name "unconnected-(U4-NC-Pad3)") (class "Default")
      (node (ref "U4") (pin "3") (pinfunction "NC_3") (pintype "passive"))
    )
  )
)
